# ASD2413.net
KiCad netlist of a schematic drawn in EAGLE
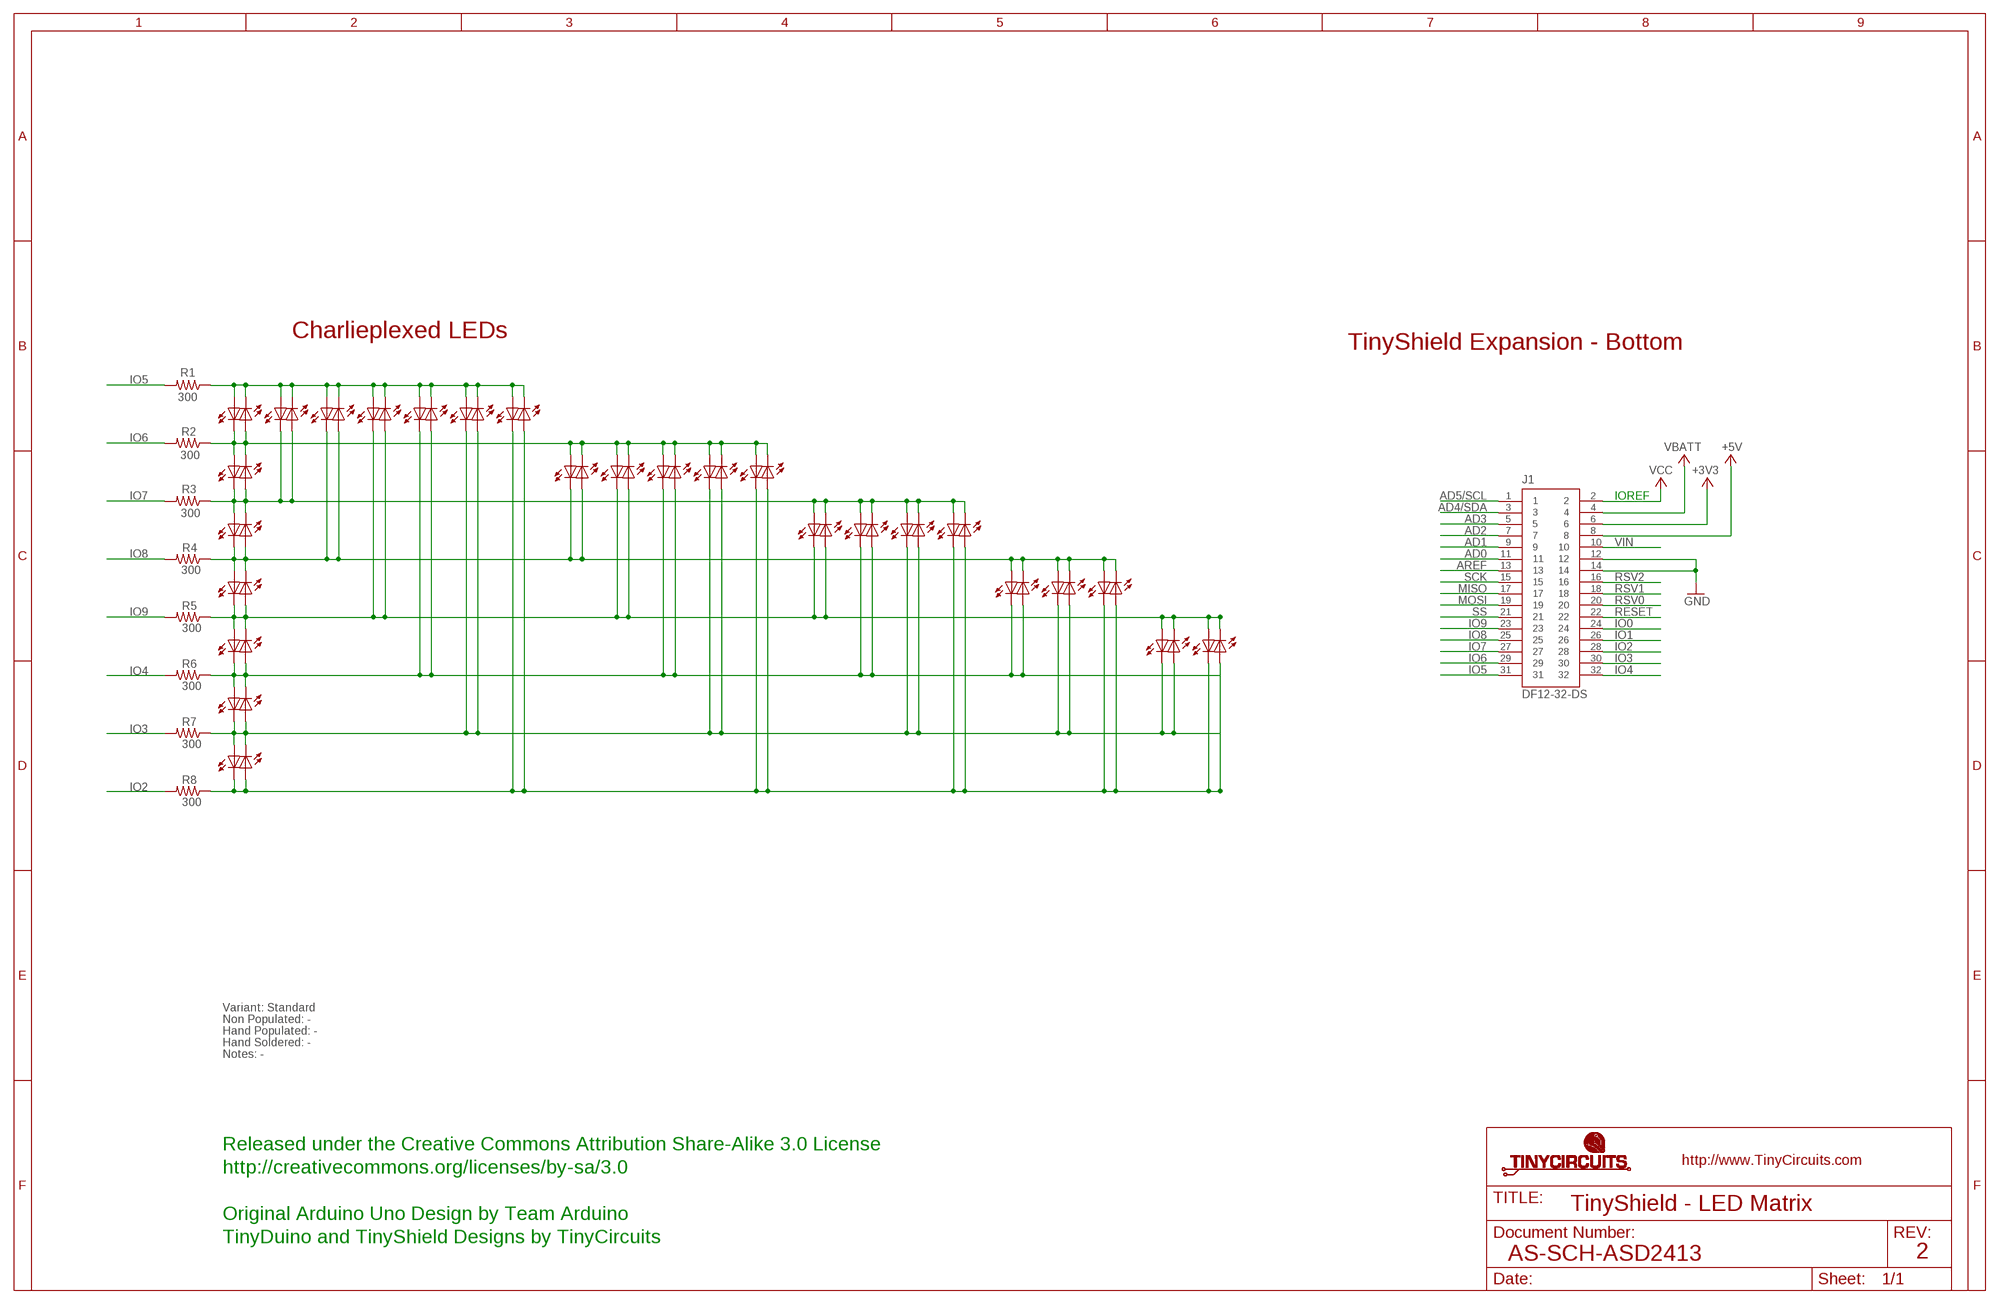
[diagram p0: schematic, sheet 1]

(export (version "E")
  (design (tool "Eeschema 10.0.6"))
  (components
    (comp (ref "D1")
      (value "GREEN")
      (footprint "eagle-import:0402_LED")
      (fields (field (name "PARTNO") "AS-ITM-00038") (field (name "PARTNO_1") "AS-ITM-00038"))
      (libsource (lib "eagle-import") (part "AS-ITM-00038"))
    )
    (comp (ref "D2")
      (value "GREEN")
      (footprint "eagle-import:0402_LED")
      (fields (field (name "PARTNO") "AS-ITM-00038") (field (name "PARTNO_1") "AS-ITM-00038"))
      (libsource (lib "eagle-import") (part "AS-ITM-00038"))
    )
    (comp (ref "D3")
      (value "GREEN")
      (footprint "eagle-import:0402_LED")
      (fields (field (name "PARTNO") "AS-ITM-00038") (field (name "PARTNO_1") "AS-ITM-00038"))
      (libsource (lib "eagle-import") (part "AS-ITM-00038"))
    )
    (comp (ref "D4")
      (value "GREEN")
      (footprint "eagle-import:0402_LED")
      (fields (field (name "PARTNO") "AS-ITM-00038") (field (name "PARTNO_1") "AS-ITM-00038"))
      (libsource (lib "eagle-import") (part "AS-ITM-00038"))
    )
    (comp (ref "D5")
      (value "GREEN")
      (footprint "eagle-import:0402_LED")
      (fields (field (name "PARTNO") "AS-ITM-00038") (field (name "PARTNO_1") "AS-ITM-00038"))
      (libsource (lib "eagle-import") (part "AS-ITM-00038"))
    )
    (comp (ref "D6")
      (value "GREEN")
      (footprint "eagle-import:0402_LED")
      (fields (field (name "PARTNO") "AS-ITM-00038") (field (name "PARTNO_1") "AS-ITM-00038"))
      (libsource (lib "eagle-import") (part "AS-ITM-00038"))
    )
    (comp (ref "D7")
      (value "GREEN")
      (footprint "eagle-import:0402_LED")
      (fields (field (name "PARTNO") "AS-ITM-00038") (field (name "PARTNO_1") "AS-ITM-00038"))
      (libsource (lib "eagle-import") (part "AS-ITM-00038"))
    )
    (comp (ref "D8")
      (value "GREEN")
      (footprint "eagle-import:0402_LED")
      (fields (field (name "PARTNO") "AS-ITM-00038") (field (name "PARTNO_1") "AS-ITM-00038"))
      (libsource (lib "eagle-import") (part "AS-ITM-00038"))
    )
    (comp (ref "D9")
      (value "GREEN")
      (footprint "eagle-import:0402_LED")
      (fields (field (name "PARTNO") "AS-ITM-00038") (field (name "PARTNO_1") "AS-ITM-00038"))
      (libsource (lib "eagle-import") (part "AS-ITM-00038"))
    )
    (comp (ref "D10")
      (value "GREEN")
      (footprint "eagle-import:0402_LED")
      (fields (field (name "PARTNO") "AS-ITM-00038") (field (name "PARTNO_1") "AS-ITM-00038"))
      (libsource (lib "eagle-import") (part "AS-ITM-00038"))
    )
    (comp (ref "D11")
      (value "GREEN")
      (footprint "eagle-import:0402_LED")
      (fields (field (name "PARTNO") "AS-ITM-00038") (field (name "PARTNO_1") "AS-ITM-00038"))
      (libsource (lib "eagle-import") (part "AS-ITM-00038"))
    )
    (comp (ref "D12")
      (value "GREEN")
      (footprint "eagle-import:0402_LED")
      (fields (field (name "PARTNO") "AS-ITM-00038") (field (name "PARTNO_1") "AS-ITM-00038"))
      (libsource (lib "eagle-import") (part "AS-ITM-00038"))
    )
    (comp (ref "D13")
      (value "GREEN")
      (footprint "eagle-import:0402_LED")
      (fields (field (name "PARTNO") "AS-ITM-00038") (field (name "PARTNO_1") "AS-ITM-00038"))
      (libsource (lib "eagle-import") (part "AS-ITM-00038"))
    )
    (comp (ref "D14")
      (value "GREEN")
      (footprint "eagle-import:0402_LED")
      (fields (field (name "PARTNO") "AS-ITM-00038") (field (name "PARTNO_1") "AS-ITM-00038"))
      (libsource (lib "eagle-import") (part "AS-ITM-00038"))
    )
    (comp (ref "D15")
      (value "GREEN")
      (footprint "eagle-import:0402_LED")
      (fields (field (name "PARTNO") "AS-ITM-00038") (field (name "PARTNO_1") "AS-ITM-00038"))
      (libsource (lib "eagle-import") (part "AS-ITM-00038"))
    )
    (comp (ref "D16")
      (value "GREEN")
      (footprint "eagle-import:0402_LED")
      (fields (field (name "PARTNO") "AS-ITM-00038") (field (name "PARTNO_1") "AS-ITM-00038"))
      (libsource (lib "eagle-import") (part "AS-ITM-00038"))
    )
    (comp (ref "D17")
      (value "GREEN")
      (footprint "eagle-import:0402_LED")
      (fields (field (name "PARTNO") "AS-ITM-00038") (field (name "PARTNO_1") "AS-ITM-00038"))
      (libsource (lib "eagle-import") (part "AS-ITM-00038"))
    )
    (comp (ref "D18")
      (value "GREEN")
      (footprint "eagle-import:0402_LED")
      (fields (field (name "PARTNO") "AS-ITM-00038") (field (name "PARTNO_1") "AS-ITM-00038"))
      (libsource (lib "eagle-import") (part "AS-ITM-00038"))
    )
    (comp (ref "D19")
      (value "GREEN")
      (footprint "eagle-import:0402_LED")
      (fields (field (name "PARTNO") "AS-ITM-00038") (field (name "PARTNO_1") "AS-ITM-00038"))
      (libsource (lib "eagle-import") (part "AS-ITM-00038"))
    )
    (comp (ref "D20")
      (value "GREEN")
      (footprint "eagle-import:0402_LED")
      (fields (field (name "PARTNO") "AS-ITM-00038") (field (name "PARTNO_1") "AS-ITM-00038"))
      (libsource (lib "eagle-import") (part "AS-ITM-00038"))
    )
    (comp (ref "D21")
      (value "GREEN")
      (footprint "eagle-import:0402_LED")
      (fields (field (name "PARTNO") "AS-ITM-00038") (field (name "PARTNO_1") "AS-ITM-00038"))
      (libsource (lib "eagle-import") (part "AS-ITM-00038"))
    )
    (comp (ref "D22")
      (value "GREEN")
      (footprint "eagle-import:0402_LED")
      (fields (field (name "PARTNO") "AS-ITM-00038") (field (name "PARTNO_1") "AS-ITM-00038"))
      (libsource (lib "eagle-import") (part "AS-ITM-00038"))
    )
    (comp (ref "D23")
      (value "GREEN")
      (footprint "eagle-import:0402_LED")
      (fields (field (name "PARTNO") "AS-ITM-00038") (field (name "PARTNO_1") "AS-ITM-00038"))
      (libsource (lib "eagle-import") (part "AS-ITM-00038"))
    )
    (comp (ref "D24")
      (value "GREEN")
      (footprint "eagle-import:0402_LED")
      (fields (field (name "PARTNO") "AS-ITM-00038") (field (name "PARTNO_1") "AS-ITM-00038"))
      (libsource (lib "eagle-import") (part "AS-ITM-00038"))
    )
    (comp (ref "D25")
      (value "GREEN")
      (footprint "eagle-import:0402_LED")
      (fields (field (name "PARTNO") "AS-ITM-00038") (field (name "PARTNO_1") "AS-ITM-00038"))
      (libsource (lib "eagle-import") (part "AS-ITM-00038"))
    )
    (comp (ref "D26")
      (value "GREEN")
      (footprint "eagle-import:0402_LED")
      (fields (field (name "PARTNO") "AS-ITM-00038") (field (name "PARTNO_1") "AS-ITM-00038"))
      (libsource (lib "eagle-import") (part "AS-ITM-00038"))
    )
    (comp (ref "D27")
      (value "GREEN")
      (footprint "eagle-import:0402_LED")
      (fields (field (name "PARTNO") "AS-ITM-00038") (field (name "PARTNO_1") "AS-ITM-00038"))
      (libsource (lib "eagle-import") (part "AS-ITM-00038"))
    )
    (comp (ref "D28")
      (value "GREEN")
      (footprint "eagle-import:0402_LED")
      (fields (field (name "PARTNO") "AS-ITM-00038") (field (name "PARTNO_1") "AS-ITM-00038"))
      (libsource (lib "eagle-import") (part "AS-ITM-00038"))
    )
    (comp (ref "D29")
      (value "GREEN")
      (footprint "eagle-import:0402_LED")
      (fields (field (name "PARTNO") "AS-ITM-00038") (field (name "PARTNO_1") "AS-ITM-00038"))
      (libsource (lib "eagle-import") (part "AS-ITM-00038"))
    )
    (comp (ref "D30")
      (value "GREEN")
      (footprint "eagle-import:0402_LED")
      (fields (field (name "PARTNO") "AS-ITM-00038") (field (name "PARTNO_1") "AS-ITM-00038"))
      (libsource (lib "eagle-import") (part "AS-ITM-00038"))
    )
    (comp (ref "D31")
      (value "GREEN")
      (footprint "eagle-import:0402_LED")
      (fields (field (name "PARTNO") "AS-ITM-00038") (field (name "PARTNO_1") "AS-ITM-00038"))
      (libsource (lib "eagle-import") (part "AS-ITM-00038"))
    )
    (comp (ref "D32")
      (value "GREEN")
      (footprint "eagle-import:0402_LED")
      (fields (field (name "PARTNO") "AS-ITM-00038") (field (name "PARTNO_1") "AS-ITM-00038"))
      (libsource (lib "eagle-import") (part "AS-ITM-00038"))
    )
    (comp (ref "D33")
      (value "GREEN")
      (footprint "eagle-import:0402_LED")
      (fields (field (name "PARTNO") "AS-ITM-00038") (field (name "PARTNO_1") "AS-ITM-00038"))
      (libsource (lib "eagle-import") (part "AS-ITM-00038"))
    )
    (comp (ref "D34")
      (value "GREEN")
      (footprint "eagle-import:0402_LED")
      (fields (field (name "PARTNO") "AS-ITM-00038") (field (name "PARTNO_1") "AS-ITM-00038"))
      (libsource (lib "eagle-import") (part "AS-ITM-00038"))
    )
    (comp (ref "D35")
      (value "GREEN")
      (footprint "eagle-import:0402_LED")
      (fields (field (name "PARTNO") "AS-ITM-00038") (field (name "PARTNO_1") "AS-ITM-00038"))
      (libsource (lib "eagle-import") (part "AS-ITM-00038"))
    )
    (comp (ref "D36")
      (value "GREEN")
      (footprint "eagle-import:0402_LED")
      (fields (field (name "PARTNO") "AS-ITM-00038") (field (name "PARTNO_1") "AS-ITM-00038"))
      (libsource (lib "eagle-import") (part "AS-ITM-00038"))
    )
    (comp (ref "D37")
      (value "GREEN")
      (footprint "eagle-import:0402_LED")
      (fields (field (name "PARTNO") "AS-ITM-00038") (field (name "PARTNO_1") "AS-ITM-00038"))
      (libsource (lib "eagle-import") (part "AS-ITM-00038"))
    )
    (comp (ref "D38")
      (value "GREEN")
      (footprint "eagle-import:0402_LED")
      (fields (field (name "PARTNO") "AS-ITM-00038") (field (name "PARTNO_1") "AS-ITM-00038"))
      (libsource (lib "eagle-import") (part "AS-ITM-00038"))
    )
    (comp (ref "D39")
      (value "GREEN")
      (footprint "eagle-import:0402_LED")
      (fields (field (name "PARTNO") "AS-ITM-00038") (field (name "PARTNO_1") "AS-ITM-00038"))
      (libsource (lib "eagle-import") (part "AS-ITM-00038"))
    )
    (comp (ref "D40")
      (value "GREEN")
      (footprint "eagle-import:0402_LED")
      (fields (field (name "PARTNO") "AS-ITM-00038") (field (name "PARTNO_1") "AS-ITM-00038"))
      (libsource (lib "eagle-import") (part "AS-ITM-00038"))
    )
    (comp (ref "D41")
      (value "GREEN")
      (footprint "eagle-import:0402_LED")
      (fields (field (name "PARTNO") "AS-ITM-00038") (field (name "PARTNO_1") "AS-ITM-00038"))
      (libsource (lib "eagle-import") (part "AS-ITM-00038"))
    )
    (comp (ref "D42")
      (value "GREEN")
      (footprint "eagle-import:0402_LED")
      (fields (field (name "PARTNO") "AS-ITM-00038") (field (name "PARTNO_1") "AS-ITM-00038"))
      (libsource (lib "eagle-import") (part "AS-ITM-00038"))
    )
    (comp (ref "D43")
      (value "GREEN")
      (footprint "eagle-import:0402_LED")
      (fields (field (name "PARTNO") "AS-ITM-00038") (field (name "PARTNO_1") "AS-ITM-00038"))
      (libsource (lib "eagle-import") (part "AS-ITM-00038"))
    )
    (comp (ref "D44")
      (value "GREEN")
      (footprint "eagle-import:0402_LED")
      (fields (field (name "PARTNO") "AS-ITM-00038") (field (name "PARTNO_1") "AS-ITM-00038"))
      (libsource (lib "eagle-import") (part "AS-ITM-00038"))
    )
    (comp (ref "D45")
      (value "GREEN")
      (footprint "eagle-import:0402_LED")
      (fields (field (name "PARTNO") "AS-ITM-00038") (field (name "PARTNO_1") "AS-ITM-00038"))
      (libsource (lib "eagle-import") (part "AS-ITM-00038"))
    )
    (comp (ref "D46")
      (value "GREEN")
      (footprint "eagle-import:0402_LED")
      (fields (field (name "PARTNO") "AS-ITM-00038") (field (name "PARTNO_1") "AS-ITM-00038"))
      (libsource (lib "eagle-import") (part "AS-ITM-00038"))
    )
    (comp (ref "D47")
      (value "GREEN")
      (footprint "eagle-import:0402_LED")
      (fields (field (name "PARTNO") "AS-ITM-00038") (field (name "PARTNO_1") "AS-ITM-00038"))
      (libsource (lib "eagle-import") (part "AS-ITM-00038"))
    )
    (comp (ref "D48")
      (value "GREEN")
      (footprint "eagle-import:0402_LED")
      (fields (field (name "PARTNO") "AS-ITM-00038") (field (name "PARTNO_1") "AS-ITM-00038"))
      (libsource (lib "eagle-import") (part "AS-ITM-00038"))
    )
    (comp (ref "D49")
      (value "GREEN")
      (footprint "eagle-import:0402_LED")
      (fields (field (name "PARTNO") "AS-ITM-00038") (field (name "PARTNO_1") "AS-ITM-00038"))
      (libsource (lib "eagle-import") (part "AS-ITM-00038"))
    )
    (comp (ref "D50")
      (value "GREEN")
      (footprint "eagle-import:0402_LED")
      (fields (field (name "PARTNO") "AS-ITM-00038") (field (name "PARTNO_1") "AS-ITM-00038"))
      (libsource (lib "eagle-import") (part "AS-ITM-00038"))
    )
    (comp (ref "D51")
      (value "GREEN")
      (footprint "eagle-import:0402_LED")
      (fields (field (name "PARTNO") "AS-ITM-00038") (field (name "PARTNO_1") "AS-ITM-00038"))
      (libsource (lib "eagle-import") (part "AS-ITM-00038"))
    )
    (comp (ref "D52")
      (value "GREEN")
      (footprint "eagle-import:0402_LED")
      (fields (field (name "PARTNO") "AS-ITM-00038") (field (name "PARTNO_1") "AS-ITM-00038"))
      (libsource (lib "eagle-import") (part "AS-ITM-00038"))
    )
    (comp (ref "D53")
      (value "GREEN")
      (footprint "eagle-import:0402_LED")
      (fields (field (name "PARTNO") "AS-ITM-00038") (field (name "PARTNO_1") "AS-ITM-00038"))
      (libsource (lib "eagle-import") (part "AS-ITM-00038"))
    )
    (comp (ref "D54")
      (value "GREEN")
      (footprint "eagle-import:0402_LED")
      (fields (field (name "PARTNO") "AS-ITM-00038") (field (name "PARTNO_1") "AS-ITM-00038"))
      (libsource (lib "eagle-import") (part "AS-ITM-00038"))
    )
    (comp (ref "J1")
      (value "DF12-32-DS")
      (footprint "eagle-import:DF12-32-DS")
      (fields (field (name "PARTNO") "AS-ITM-00012") (field (name "PARTNO_1") "AS-ITM-00012"))
      (libsource (lib "eagle-import") (part "AS-ITM-00012"))
    )
    (comp (ref "R1")
      (value "300")
      (footprint "eagle-import:0402")
      (fields (field (name "PARTNO") "AS-ITM-00016") (field (name "PARTNO_1") "AS-ITM-00016"))
      (libsource (lib "eagle-import") (part "AS-ITM-00016"))
    )
    (comp (ref "R2")
      (value "300")
      (footprint "eagle-import:0402")
      (fields (field (name "PARTNO") "AS-ITM-00016"))
      (libsource (lib "eagle-import") (part "AS-ITM-00016"))
    )
    (comp (ref "R3")
      (value "300")
      (footprint "eagle-import:0402")
      (fields (field (name "PARTNO") "AS-ITM-00016"))
      (libsource (lib "eagle-import") (part "AS-ITM-00016"))
    )
    (comp (ref "R4")
      (value "300")
      (footprint "eagle-import:0402")
      (fields (field (name "PARTNO") "AS-ITM-00016"))
      (libsource (lib "eagle-import") (part "AS-ITM-00016"))
    )
    (comp (ref "R5")
      (value "300")
      (footprint "eagle-import:0402")
      (fields (field (name "PARTNO") "AS-ITM-00016"))
      (libsource (lib "eagle-import") (part "AS-ITM-00016"))
    )
    (comp (ref "R6")
      (value "300")
      (footprint "eagle-import:0402")
      (fields (field (name "PARTNO") "AS-ITM-00016") (field (name "PARTNO_1") "AS-ITM-00016"))
      (libsource (lib "eagle-import") (part "AS-ITM-00016"))
    )
    (comp (ref "R7")
      (value "300")
      (footprint "eagle-import:0402")
      (fields (field (name "PARTNO") "AS-ITM-00016") (field (name "PARTNO_1") "AS-ITM-00016"))
      (libsource (lib "eagle-import") (part "AS-ITM-00016"))
    )
    (comp (ref "R8")
      (value "300")
      (footprint "eagle-import:0402")
      (fields (field (name "PARTNO") "AS-ITM-00016") (field (name "PARTNO_1") "AS-ITM-00016"))
      (libsource (lib "eagle-import") (part "AS-ITM-00016"))
    )
  )
  (nets
    (net (code "1") (name "+3V3") (class "Default")
      (node (ref "J1") (pin "6") (pinfunction "6_6") (pintype "bidirectional"))
    )
    (net (code "2") (name "+5V") (class "Default")
      (node (ref "J1") (pin "8") (pinfunction "8_8") (pintype "bidirectional"))
    )
    (net (code "3") (name "/AD0") (class "Default")
      (node (ref "J1") (pin "11") (pinfunction "11_11") (pintype "bidirectional"))
    )
    (net (code "4") (name "/AD1") (class "Default")
      (node (ref "J1") (pin "9") (pinfunction "9_9") (pintype "bidirectional"))
    )
    (net (code "5") (name "/AD2") (class "Default")
      (node (ref "J1") (pin "7") (pinfunction "7_7") (pintype "bidirectional"))
    )
    (net (code "6") (name "/AD3") (class "Default")
      (node (ref "J1") (pin "5") (pinfunction "5_5") (pintype "bidirectional"))
    )
    (net (code "7") (name "/AD4{slash}SDA") (class "Default")
      (node (ref "J1") (pin "3") (pinfunction "3_3") (pintype "bidirectional"))
    )
    (net (code "8") (name "/AD5{slash}SCL") (class "Default")
      (node (ref "J1") (pin "1") (pinfunction "1_1") (pintype "bidirectional"))
    )
    (net (code "9") (name "/AREF") (class "Default")
      (node (ref "J1") (pin "13") (pinfunction "13_13") (pintype "bidirectional"))
    )
    (net (code "10") (name "/IO0") (class "Default")
      (node (ref "J1") (pin "24") (pinfunction "24_24") (pintype "bidirectional"))
    )
    (net (code "11") (name "/IO1") (class "Default")
      (node (ref "J1") (pin "26") (pinfunction "26_26") (pintype "bidirectional"))
    )
    (net (code "12") (name "/IO2") (class "Default")
      (node (ref "J1") (pin "28") (pinfunction "28_28") (pintype "bidirectional"))
      (node (ref "R8") (pin "2") (pinfunction "2_2") (pintype "passive"))
    )
    (net (code "13") (name "/IO3") (class "Default")
      (node (ref "J1") (pin "30") (pinfunction "30_30") (pintype "bidirectional"))
      (node (ref "R7") (pin "2") (pinfunction "2_2") (pintype "passive"))
    )
    (net (code "14") (name "/IO4") (class "Default")
      (node (ref "J1") (pin "32") (pinfunction "32_32") (pintype "bidirectional"))
      (node (ref "R6") (pin "2") (pinfunction "2_2") (pintype "passive"))
    )
    (net (code "15") (name "/IO5") (class "Default")
      (node (ref "J1") (pin "31") (pinfunction "31_31") (pintype "bidirectional"))
      (node (ref "R1") (pin "2") (pinfunction "2_2") (pintype "passive"))
    )
    (net (code "16") (name "/IO6") (class "Default")
      (node (ref "J1") (pin "29") (pinfunction "29_29") (pintype "bidirectional"))
      (node (ref "R2") (pin "2") (pinfunction "2_2") (pintype "passive"))
    )
    (net (code "17") (name "/IO7") (class "Default")
      (node (ref "J1") (pin "27") (pinfunction "27_27") (pintype "bidirectional"))
      (node (ref "R3") (pin "2") (pinfunction "2_2") (pintype "passive"))
    )
    (net (code "18") (name "/IO8") (class "Default")
      (node (ref "J1") (pin "25") (pinfunction "25_25") (pintype "bidirectional"))
      (node (ref "R4") (pin "2") (pinfunction "2_2") (pintype "passive"))
    )
    (net (code "19") (name "/IO9") (class "Default")
      (node (ref "J1") (pin "23") (pinfunction "23_23") (pintype "bidirectional"))
      (node (ref "R5") (pin "2") (pinfunction "2_2") (pintype "passive"))
    )
    (net (code "20") (name "/MISO") (class "Default")
      (node (ref "J1") (pin "17") (pinfunction "17_17") (pintype "bidirectional"))
    )
    (net (code "21") (name "/MOSI") (class "Default")
      (node (ref "J1") (pin "19") (pinfunction "19_19") (pintype "bidirectional"))
    )
    (net (code "22") (name "/RESET") (class "Default")
      (node (ref "J1") (pin "22") (pinfunction "22_22") (pintype "bidirectional"))
    )
    (net (code "23") (name "/RSV0") (class "Default")
      (node (ref "J1") (pin "20") (pinfunction "20_20") (pintype "bidirectional"))
    )
    (net (code "24") (name "/RSV1") (class "Default")
      (node (ref "J1") (pin "18") (pinfunction "18_18") (pintype "bidirectional"))
    )
    (net (code "25") (name "/RSV2") (class "Default")
      (node (ref "J1") (pin "16") (pinfunction "16_16") (pintype "bidirectional"))
    )
    (net (code "26") (name "/SCK") (class "Default")
      (node (ref "J1") (pin "15") (pinfunction "15_15") (pintype "bidirectional"))
    )
    (net (code "27") (name "/SS") (class "Default")
      (node (ref "J1") (pin "21") (pinfunction "21_21") (pintype "bidirectional"))
    )
    (net (code "28") (name "/VIN") (class "Default")
      (node (ref "J1") (pin "10") (pinfunction "10_10") (pintype "bidirectional"))
    )
    (net (code "29") (name "GND") (class "Default")
      (node (ref "J1") (pin "12") (pinfunction "12_12") (pintype "bidirectional"))
      (node (ref "J1") (pin "14") (pinfunction "14_14") (pintype "bidirectional"))
    )
    (net (code "30") (name "Net-(D1-A)") (class "Default")
      (node (ref "D1") (pin "1") (pinfunction "A_1") (pintype "passive"))
      (node (ref "D15") (pin "1") (pinfunction "A_1") (pintype "passive"))
      (node (ref "D16") (pin "2") (pinfunction "C_2") (pintype "passive"))
      (node (ref "D17") (pin "1") (pinfunction "A_1") (pintype "passive"))
      (node (ref "D18") (pin "2") (pinfunction "C_2") (pintype "passive"))
      (node (ref "D19") (pin "1") (pinfunction "A_1") (pintype "passive"))
      (node (ref "D20") (pin "2") (pinfunction "C_2") (pintype "passive"))
      (node (ref "D21") (pin "1") (pinfunction "A_1") (pintype "passive"))
      (node (ref "D22") (pin "2") (pinfunction "C_2") (pintype "passive"))
      (node (ref "D23") (pin "1") (pinfunction "A_1") (pintype "passive"))
      (node (ref "D24") (pin "2") (pinfunction "C_2") (pintype "passive"))
      (node (ref "D25") (pin "1") (pinfunction "A_1") (pintype "passive"))
      (node (ref "D26") (pin "2") (pinfunction "C_2") (pintype "passive"))
      (node (ref "D8") (pin "2") (pinfunction "C_2") (pintype "passive"))
      (node (ref "R1") (pin "1") (pinfunction "1_1") (pintype "passive"))
    )
    (net (code "31") (name "Net-(D1-C)") (class "Default")
      (node (ref "D1") (pin "2") (pinfunction "C_2") (pintype "passive"))
      (node (ref "D2") (pin "1") (pinfunction "A_1") (pintype "passive"))
      (node (ref "D27") (pin "1") (pinfunction "A_1") (pintype "passive"))
      (node (ref "D28") (pin "2") (pinfunction "C_2") (pintype "passive"))
      (node (ref "D29") (pin "1") (pinfunction "A_1") (pintype "passive"))
      (node (ref "D30") (pin "2") (pinfunction "C_2") (pintype "passive"))
      (node (ref "D31") (pin "1") (pinfunction "A_1") (pintype "passive"))
      (node (ref "D32") (pin "2") (pinfunction "C_2") (pintype "passive"))
      (node (ref "D33") (pin "1") (pinfunction "A_1") (pintype "passive"))
      (node (ref "D34") (pin "2") (pinfunction "C_2") (pintype "passive"))
      (node (ref "D35") (pin "1") (pinfunction "A_1") (pintype "passive"))
      (node (ref "D36") (pin "2") (pinfunction "C_2") (pintype "passive"))
      (node (ref "D8") (pin "1") (pinfunction "A_1") (pintype "passive"))
      (node (ref "D9") (pin "2") (pinfunction "C_2") (pintype "passive"))
      (node (ref "R2") (pin "1") (pinfunction "1_1") (pintype "passive"))
    )
    (net (code "32") (name "Net-(D10-A)") (class "Default")
      (node (ref "D10") (pin "1") (pinfunction "A_1") (pintype "passive"))
      (node (ref "D11") (pin "2") (pinfunction "C_2") (pintype "passive"))
      (node (ref "D17") (pin "2") (pinfunction "C_2") (pintype "passive"))
      (node (ref "D18") (pin "1") (pinfunction "A_1") (pintype "passive"))
      (node (ref "D27") (pin "2") (pinfunction "C_2") (pintype "passive"))
      (node (ref "D28") (pin "1") (pinfunction "A_1") (pintype "passive"))
      (node (ref "D3") (pin "2") (pinfunction "C_2") (pintype "passive"))
      (node (ref "D4") (pin "1") (pinfunction "A_1") (pintype "passive"))
      (node (ref "D45") (pin "1") (pinfunction "A_1") (pintype "passive"))
      (node (ref "D46") (pin "2") (pinfunction "C_2") (pintype "passive"))
      (node (ref "D47") (pin "1") (pinfunction "A_1") (pintype "passive"))
      (node (ref "D48") (pin "2") (pinfunction "C_2") (pintype "passive"))
      (node (ref "D49") (pin "1") (pinfunction "A_1") (pintype "passive"))
      (node (ref "D50") (pin "2") (pinfunction "C_2") (pintype "passive"))
      (node (ref "R4") (pin "1") (pinfunction "1_1") (pintype "passive"))
    )
    (net (code "33") (name "Net-(D10-C)") (class "Default")
      (node (ref "D10") (pin "2") (pinfunction "C_2") (pintype "passive"))
      (node (ref "D15") (pin "2") (pinfunction "C_2") (pintype "passive"))
      (node (ref "D16") (pin "1") (pinfunction "A_1") (pintype "passive"))
      (node (ref "D2") (pin "2") (pinfunction "C_2") (pintype "passive"))
      (node (ref "D3") (pin "1") (pinfunction "A_1") (pintype "passive"))
      (node (ref "D37") (pin "1") (pinfunction "A_1") (pintype "passive"))
      (node (ref "D38") (pin "2") (pinfunction "C_2") (pintype "passive"))
      (node (ref "D39") (pin "1") (pinfunction "A_1") (pintype "passive"))
      (node (ref "D40") (pin "2") (pinfunction "C_2") (pintype "passive"))
      (node (ref "D41") (pin "1") (pinfunction "A_1") (pintype "passive"))
      (node (ref "D42") (pin "2") (pinfunction "C_2") (pintype "passive"))
      (node (ref "D43") (pin "1") (pinfunction "A_1") (pintype "passive"))
      (node (ref "D44") (pin "2") (pinfunction "C_2") (pintype "passive"))
      (node (ref "D9") (pin "1") (pinfunction "A_1") (pintype "passive"))
      (node (ref "R3") (pin "1") (pinfunction "1_1") (pintype "passive"))
    )
    (net (code "34") (name "Net-(D11-A)") (class "Default")
      (node (ref "D11") (pin "1") (pinfunction "A_1") (pintype "passive"))
      (node (ref "D12") (pin "2") (pinfunction "C_2") (pintype "passive"))
      (node (ref "D19") (pin "2") (pinfunction "C_2") (pintype "passive"))
      (node (ref "D20") (pin "1") (pinfunction "A_1") (pintype "passive"))
      (node (ref "D29") (pin "2") (pinfunction "C_2") (pintype "passive"))
      (node (ref "D30") (pin "1") (pinfunction "A_1") (pintype "passive"))
      (node (ref "D37") (pin "2") (pinfunction "C_2") (pintype "passive"))
      (node (ref "D38") (pin "1") (pinfunction "A_1") (pintype "passive"))
      (node (ref "D4") (pin "2") (pinfunction "C_2") (pintype "passive"))
      (node (ref "D5") (pin "1") (pinfunction "A_1") (pintype "passive"))
      (node (ref "D51") (pin "1") (pinfunction "A_1") (pintype "passive"))
      (node (ref "D52") (pin "2") (pinfunction "C_2") (pintype "passive"))
      (node (ref "D53") (pin "1") (pinfunction "A_1") (pintype "passive"))
      (node (ref "D54") (pin "2") (pinfunction "C_2") (pintype "passive"))
      (node (ref "R5") (pin "1") (pinfunction "1_1") (pintype "passive"))
    )
    (net (code "35") (name "Net-(D12-A)") (class "Default")
      (node (ref "D12") (pin "1") (pinfunction "A_1") (pintype "passive"))
      (node (ref "D13") (pin "2") (pinfunction "C_2") (pintype "passive"))
      (node (ref "D21") (pin "2") (pinfunction "C_2") (pintype "passive"))
      (node (ref "D22") (pin "1") (pinfunction "A_1") (pintype "passive"))
      (node (ref "D31") (pin "2") (pinfunction "C_2") (pintype "passive"))
      (node (ref "D32") (pin "1") (pinfunction "A_1") (pintype "passive"))
      (node (ref "D39") (pin "2") (pinfunction "C_2") (pintype "passive"))
      (node (ref "D40") (pin "1") (pinfunction "A_1") (pintype "passive"))
      (node (ref "D45") (pin "2") (pinfunction "C_2") (pintype "passive"))
      (node (ref "D46") (pin "1") (pinfunction "A_1") (pintype "passive"))
      (node (ref "D5") (pin "2") (pinfunction "C_2") (pintype "passive"))
      (node (ref "D6") (pin "1") (pinfunction "A_1") (pintype "passive"))
      (node (ref "R6") (pin "1") (pinfunction "1_1") (pintype "passive"))
    )
    (net (code "36") (name "Net-(D13-A)") (class "Default")
      (node (ref "D13") (pin "1") (pinfunction "A_1") (pintype "passive"))
      (node (ref "D14") (pin "2") (pinfunction "C_2") (pintype "passive"))
      (node (ref "D23") (pin "2") (pinfunction "C_2") (pintype "passive"))
      (node (ref "D24") (pin "1") (pinfunction "A_1") (pintype "passive"))
      (node (ref "D33") (pin "2") (pinfunction "C_2") (pintype "passive"))
      (node (ref "D34") (pin "1") (pinfunction "A_1") (pintype "passive"))
      (node (ref "D41") (pin "2") (pinfunction "C_2") (pintype "passive"))
      (node (ref "D42") (pin "1") (pinfunction "A_1") (pintype "passive"))
      (node (ref "D47") (pin "2") (pinfunction "C_2") (pintype "passive"))
      (node (ref "D48") (pin "1") (pinfunction "A_1") (pintype "passive"))
      (node (ref "D51") (pin "2") (pinfunction "C_2") (pintype "passive"))
      (node (ref "D52") (pin "1") (pinfunction "A_1") (pintype "passive"))
      (node (ref "D6") (pin "2") (pinfunction "C_2") (pintype "passive"))
      (node (ref "D7") (pin "1") (pinfunction "A_1") (pintype "passive"))
      (node (ref "R7") (pin "1") (pinfunction "1_1") (pintype "passive"))
    )
    (net (code "37") (name "Net-(D14-A)") (class "Default")
      (node (ref "D14") (pin "1") (pinfunction "A_1") (pintype "passive"))
      (node (ref "D25") (pin "2") (pinfunction "C_2") (pintype "passive"))
      (node (ref "D26") (pin "1") (pinfunction "A_1") (pintype "passive"))
      (node (ref "D35") (pin "2") (pinfunction "C_2") (pintype "passive"))
      (node (ref "D36") (pin "1") (pinfunction "A_1") (pintype "passive"))
      (node (ref "D43") (pin "2") (pinfunction "C_2") (pintype "passive"))
      (node (ref "D44") (pin "1") (pinfunction "A_1") (pintype "passive"))
      (node (ref "D49") (pin "2") (pinfunction "C_2") (pintype "passive"))
      (node (ref "D50") (pin "1") (pinfunction "A_1") (pintype "passive"))
      (node (ref "D53") (pin "2") (pinfunction "C_2") (pintype "passive"))
      (node (ref "D54") (pin "1") (pinfunction "A_1") (pintype "passive"))
      (node (ref "D7") (pin "2") (pinfunction "C_2") (pintype "passive"))
      (node (ref "R8") (pin "1") (pinfunction "1_1") (pintype "passive"))
    )
    (net (code "38") (name "VBATT") (class "Default")
      (node (ref "J1") (pin "4") (pinfunction "4_4") (pintype "bidirectional"))
    )
    (net (code "39") (name "VCC") (class "Default")
      (node (ref "J1") (pin "2") (pinfunction "2_2") (pintype "bidirectional"))
    )
  )
)
